# 3V3_voltage_regulato.net
KiCad netlist of a schematic drawn in Altium Designer
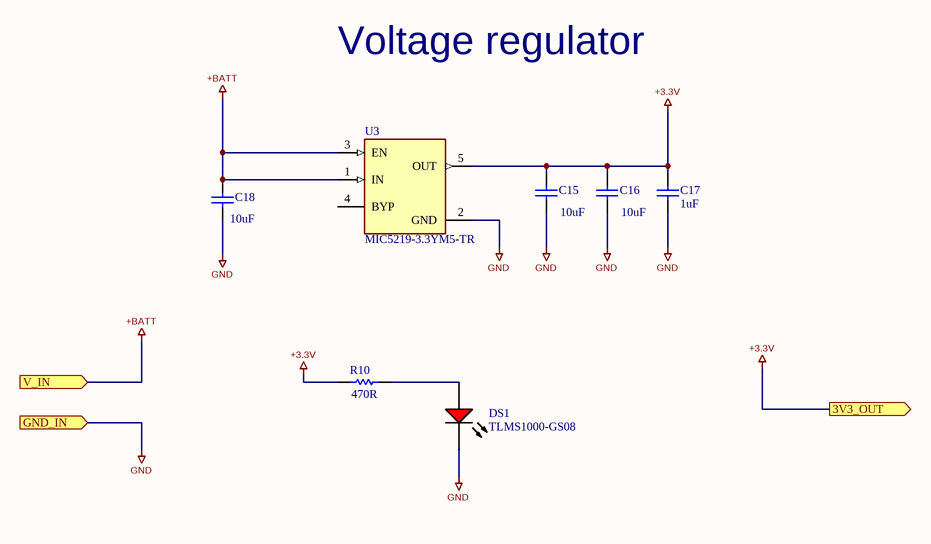
[diagram p0: 3V3 voltage regulato.SchDoc]

(export (version "E")
  (design (tool "Eeschema 10.0.6"))
  (components
    (comp (ref "C15")
      (value "10uF")
      (footprint "CAPC1608X90X35NL10T15")
      (fields (field (name "PART NUMBER") "GRM188R60J106ME47D") (field (name "MANUFACTURER") "Murata"))
      (libsource (lib "Altium Content Vault") (part "CAP"))
    )
    (comp (ref "C16")
      (value "10uF")
      (footprint "CAPC1608X90X35NL10T15")
      (fields (field (name "PART NUMBER") "GRM188R60J106ME47D") (field (name "MANUFACTURER") "Murata"))
      (libsource (lib "Altium Content Vault") (part "CAP"))
    )
    (comp (ref "C17")
      (value "1uF")
      (footprint "CAPC1608X90X35LL10T15")
      (fields (field (name "MANUFACTURER") "Murata") (field (name "PART NUMBER") "GRM188R61E105KA12D"))
      (libsource (lib "Altium Content Vault") (part "CAP"))
    )
    (comp (ref "C18")
      (value "10uF")
      (footprint "CAPC1608X90X35NL10T15")
      (fields (field (name "PART NUMBER") "GRM188R60J106ME47D") (field (name "MANUFACTURER") "Murata"))
      (libsource (lib "Altium Content Vault") (part "CAP"))
    )
    (comp (ref "DS1")
      (value "TLMS1000-GS08")
      (footprint "VISH-TLMS1000_V")
      (description "Low Current LED, 40 mW, 1.8 V, -40 to 100 degC, 2-Pin SMD (0603), RoHS, Tape and Reel")
      (fields (field (name "MANUFACTURER") "Vishay"))
      (libsource (lib "Altium Content Vault") (part "LED-RED-AK-2"))
    )
    (comp (ref "R10")
      (value "470R")
      (footprint "RESC1608X55X25LL10T15")
      (libsource (lib "Altium Content Vault") (part "RES-2"))
    )
    (comp (ref "U3")
      (value "MIC5219-3.3YM5-TR")
      (footprint "FP-SOT23-5LD-PL-1-IPC_C")
      (description "IC REG LINEAR 3.3V 500MA SOT23-5")
      (libsource (lib "Altium Content Vault") (part "16b36b16d6b7b40c29ab14718bc3058"))
    )
  )
  (nets
    (net (code "1") (name "+3.3V") (class "Default")
      (node (ref "C15") (pin "2") (pinfunction "2_2") (pintype "passive"))
      (node (ref "C16") (pin "2") (pinfunction "2_2") (pintype "passive"))
      (node (ref "C17") (pin "2") (pinfunction "2_2") (pintype "passive"))
      (node (ref "R10") (pin "1") (pinfunction "1_1") (pintype "passive"))
      (node (ref "U3") (pin "5") (pinfunction "OUT_5") (pintype "output"))
    )
    (net (code "2") (name "+BATT") (class "Default")
      (node (ref "C18") (pin "2") (pinfunction "2_2") (pintype "passive"))
      (node (ref "U3") (pin "1") (pinfunction "IN_1") (pintype "input"))
      (node (ref "U3") (pin "3") (pinfunction "EN_3") (pintype "input"))
    )
    (net (code "3") (name "GND") (class "Default")
      (node (ref "C15") (pin "1") (pinfunction "1_1") (pintype "passive"))
      (node (ref "C16") (pin "1") (pinfunction "1_1") (pintype "passive"))
      (node (ref "C17") (pin "1") (pinfunction "1_1") (pintype "passive"))
      (node (ref "C18") (pin "1") (pinfunction "1_1") (pintype "passive"))
      (node (ref "DS1") (pin "2") (pinfunction "K_2") (pintype "passive"))
      (node (ref "U3") (pin "2") (pinfunction "GND_2") (pintype "power_in"))
    )
    (net (code "4") (name "Net-(DS1-A)") (class "Default")
      (node (ref "DS1") (pin "1") (pinfunction "A_1") (pintype "passive"))
      (node (ref "R10") (pin "2") (pinfunction "2_2") (pintype "passive"))
    )
    (net (code "5") (name "unconnected-(U3-BYP-Pad4)") (class "Default")
      (node (ref "U3") (pin "4") (pinfunction "BYP_4") (pintype "passive"))
    )
  )
)
